# sparkpunk.net
KiCad netlist of a schematic drawn in EAGLE
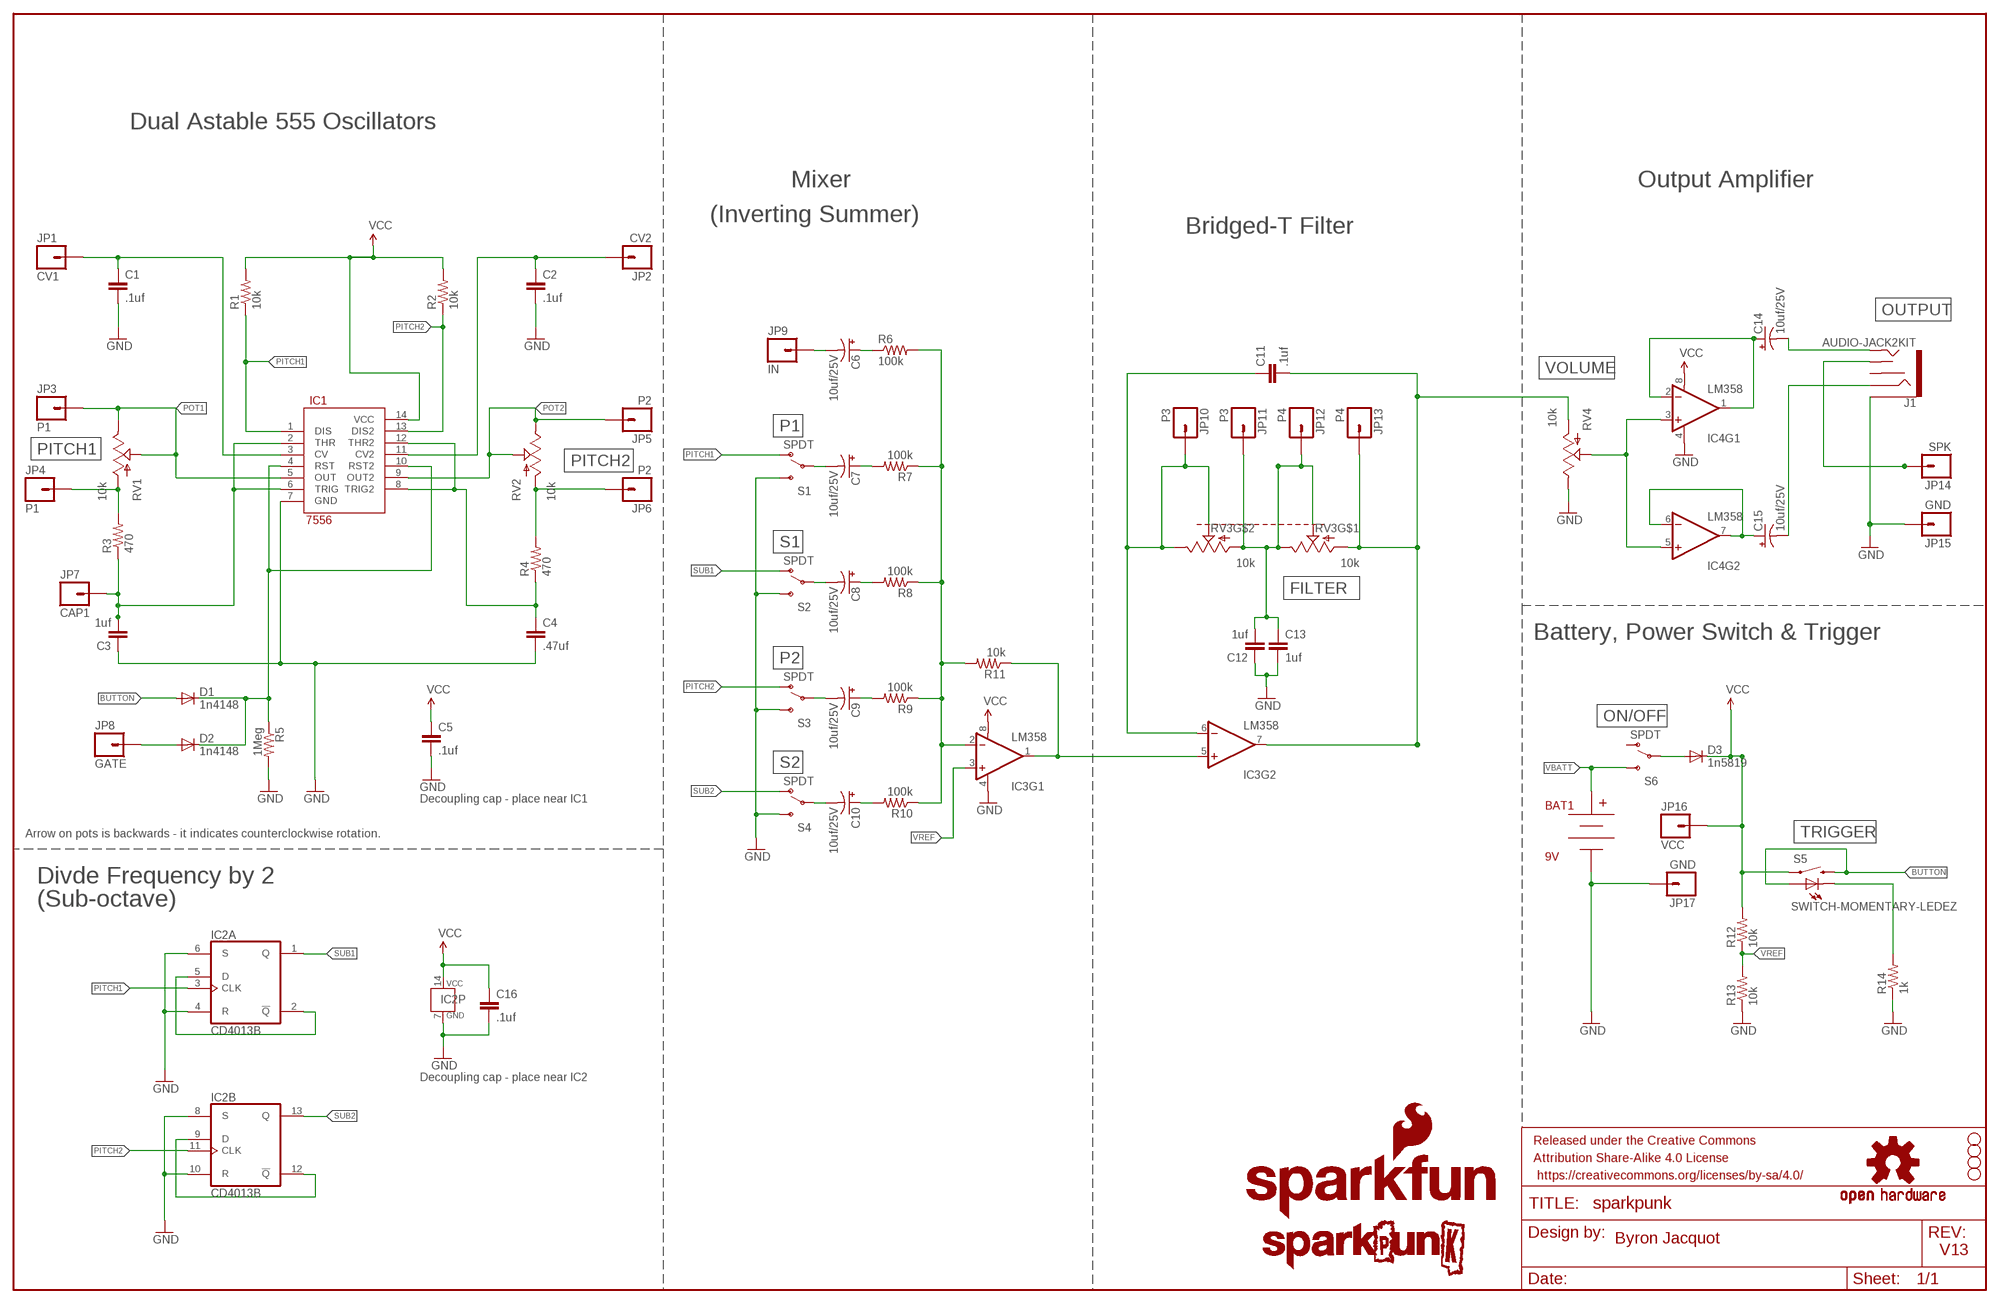
[diagram p0: schematic, sheet 1]

(export (version "E")
  (design (tool "Eeschema 10.0.6"))
  (components
    (comp (ref "BAT1")
      (value "9V")
      (footprint "eagle-import:BC9VPC_KIT")
      (libsource (lib "eagle-import") (part "BC9VPCKIT_SOLDERMASK"))
    )
    (comp (ref "C1")
      (value ".1uf")
      (footprint "eagle-import:CAP-PTH-SMALL-KIT")
      (libsource (lib "eagle-import") (part "CAPKIT"))
    )
    (comp (ref "C2")
      (value ".1uf")
      (footprint "eagle-import:CAP-PTH-SMALL-KIT")
      (libsource (lib "eagle-import") (part "CAPKIT"))
    )
    (comp (ref "C3")
      (value "1uf")
      (footprint "eagle-import:CAP-PTH-SMALL-KIT")
      (libsource (lib "eagle-import") (part "CAPKIT"))
    )
    (comp (ref "C4")
      (value ".47uf")
      (footprint "eagle-import:CAP-PTH-SMALL-KIT")
      (libsource (lib "eagle-import") (part "CAPKIT"))
    )
    (comp (ref "C5")
      (value ".1uf")
      (footprint "eagle-import:CAP-PTH-SMALL-KIT")
      (libsource (lib "eagle-import") (part "CAPKIT"))
    )
    (comp (ref "C6")
      (value "10uf/25V")
      (footprint "eagle-import:CPOL-RADIAL-10UF-25V-KIT")
      (libsource (lib "eagle-import") (part "10UF-25V-20%(PTH)KIT"))
    )
    (comp (ref "C7")
      (value "10uf/25V")
      (footprint "eagle-import:CPOL-RADIAL-10UF-25V-KIT")
      (libsource (lib "eagle-import") (part "10UF-25V-20%(PTH)KIT"))
    )
    (comp (ref "C8")
      (value "10uf/25V")
      (footprint "eagle-import:CPOL-RADIAL-10UF-25V-KIT")
      (libsource (lib "eagle-import") (part "10UF-25V-20%(PTH)KIT"))
    )
    (comp (ref "C9")
      (value "10uf/25V")
      (footprint "eagle-import:CPOL-RADIAL-10UF-25V-KIT")
      (libsource (lib "eagle-import") (part "10UF-25V-20%(PTH)KIT"))
    )
    (comp (ref "C10")
      (value "10uf/25V")
      (footprint "eagle-import:CPOL-RADIAL-10UF-25V-KIT")
      (libsource (lib "eagle-import") (part "10UF-25V-20%(PTH)KIT"))
    )
    (comp (ref "C11")
      (value ".1uf")
      (footprint "eagle-import:CAP-PTH-SMALL-KIT")
      (libsource (lib "eagle-import") (part "CAPKIT"))
    )
    (comp (ref "C12")
      (value "1uf")
      (footprint "eagle-import:CAP-PTH-SMALL-KIT")
      (libsource (lib "eagle-import") (part "CAPKIT"))
    )
    (comp (ref "C13")
      (value "1uf")
      (footprint "eagle-import:CAP-PTH-SMALL-KIT")
      (libsource (lib "eagle-import") (part "CAPKIT"))
    )
    (comp (ref "C14")
      (value "10uf/25V")
      (footprint "eagle-import:CPOL-RADIAL-10UF-25V-KIT")
      (libsource (lib "eagle-import") (part "10UF-25V-20%(PTH)KIT"))
    )
    (comp (ref "C15")
      (value "10uf/25V")
      (footprint "eagle-import:CPOL-RADIAL-10UF-25V-KIT")
      (libsource (lib "eagle-import") (part "10UF-25V-20%(PTH)KIT"))
    )
    (comp (ref "C16")
      (value ".1uf")
      (footprint "eagle-import:CAP-PTH-SMALL-KIT")
      (libsource (lib "eagle-import") (part "CAPKIT"))
    )
    (comp (ref "D1")
      (value "1n4148")
      (footprint "eagle-import:DIODE-1N4148-KIT")
      (libsource (lib "eagle-import") (part "DIODEKIT"))
    )
    (comp (ref "D2")
      (value "1n4148")
      (footprint "eagle-import:DIODE-1N4148-KIT")
      (libsource (lib "eagle-import") (part "DIODEKIT"))
    )
    (comp (ref "D3")
      (value "1n5819")
      (footprint "eagle-import:DIODE-1N4001-KIT")
      (libsource (lib "eagle-import") (part "DIODE"))
    )
    (comp (ref "FRAME1")
      (value "FRAME-LEDGER")
      (footprint "eagle-import:CREATIVE_COMMONS")
      (libsource (lib "eagle-import") (part "FRAME-LEDGER"))
    )
    (comp (ref "IC1")
      (value "7556")
      (footprint "eagle-import:DIL14-KIT")
      (libsource (lib "eagle-import") (part "556KIT"))
    )
    (comp (ref "IC2")
      (value "CD4013B")
      (footprint "eagle-import:DIL14-KIT")
      (libsource (lib "eagle-import") (part "CD4013"))
    )
    (comp (ref "IC3")
      (value "LM358")
      (footprint "eagle-import:DIP08-KIT")
      (libsource (lib "eagle-import") (part "LM358KIT"))
    )
    (comp (ref "IC4")
      (value "LM358")
      (footprint "eagle-import:DIP08-KIT")
      (libsource (lib "eagle-import") (part "LM358KIT"))
    )
    (comp (ref "J1")
      (value "AUDIO-JACK2KIT")
      (footprint "eagle-import:AUDIO-JACK-KIT")
      (libsource (lib "eagle-import") (part "AUDIO-JACK2KIT"))
    )
    (comp (ref "JP1")
      (value "CV1")
      (footprint "eagle-import:1X01NS")
      (libsource (lib "eagle-import") (part "M01SMDNS"))
    )
    (comp (ref "JP2")
      (value "CV2")
      (footprint "eagle-import:1X01NS")
      (libsource (lib "eagle-import") (part "M01SMDNS"))
    )
    (comp (ref "JP3")
      (value "P1")
      (footprint "eagle-import:1X01NS")
      (libsource (lib "eagle-import") (part "M01SMDNS"))
    )
    (comp (ref "JP4")
      (value "P1")
      (footprint "eagle-import:1X01NS")
      (libsource (lib "eagle-import") (part "M01SMDNS"))
    )
    (comp (ref "JP5")
      (value "P2")
      (footprint "eagle-import:1X01NS")
      (libsource (lib "eagle-import") (part "M01SMDNS"))
    )
    (comp (ref "JP6")
      (value "P2")
      (footprint "eagle-import:1X01NS")
      (libsource (lib "eagle-import") (part "M01SMDNS"))
    )
    (comp (ref "JP7")
      (value "CAP1")
      (footprint "eagle-import:1X01NS")
      (libsource (lib "eagle-import") (part "M01SMDNS"))
    )
    (comp (ref "JP8")
      (value "GATE")
      (footprint "eagle-import:1X01NS")
      (libsource (lib "eagle-import") (part "M01SMDNS"))
    )
    (comp (ref "JP9")
      (value "IN")
      (footprint "eagle-import:1X01NS")
      (libsource (lib "eagle-import") (part "M01SMDNS"))
    )
    (comp (ref "JP10")
      (value "P3")
      (footprint "eagle-import:1X01NS")
      (libsource (lib "eagle-import") (part "M01SMDNS"))
    )
    (comp (ref "JP11")
      (value "P3")
      (footprint "eagle-import:1X01NS")
      (libsource (lib "eagle-import") (part "M01SMDNS"))
    )
    (comp (ref "JP12")
      (value "P4")
      (footprint "eagle-import:1X01NS")
      (libsource (lib "eagle-import") (part "M01SMDNS"))
    )
    (comp (ref "JP13")
      (value "P4")
      (footprint "eagle-import:1X01NS")
      (libsource (lib "eagle-import") (part "M01SMDNS"))
    )
    (comp (ref "JP14")
      (value "SPK")
      (footprint "eagle-import:1X01NS")
      (libsource (lib "eagle-import") (part "M01SMDNS"))
    )
    (comp (ref "JP15")
      (value "GND")
      (footprint "eagle-import:1X01NS")
      (libsource (lib "eagle-import") (part "M01SMDNS"))
    )
    (comp (ref "JP16")
      (value "VCC")
      (footprint "eagle-import:1X01NS")
      (libsource (lib "eagle-import") (part "M01SMDNS"))
    )
    (comp (ref "JP17")
      (value "GND")
      (footprint "eagle-import:1X01NS")
      (libsource (lib "eagle-import") (part "M01SMDNS"))
    )
    (comp (ref "LOGO1")
      (value "SFE_LOGO_NAME_FLAME.2_INCH")
      (footprint "eagle-import:SFE_LOGO_NAME_FLAME_.2")
      (libsource (lib "eagle-import") (part "SFE_LOGO_NAME_FLAME.2_INCH"))
    )
    (comp (ref "LOGO2")
      (value "SPARKPUNK_LOGO.1INCH_TALL")
      (footprint "eagle-import:SPARKPUNK_LOGO_.1")
      (libsource (lib "eagle-import") (part "SPARKPUNK_LOGO.1INCH_TALL"))
    )
    (comp (ref "LOGO3")
      (value "OSHW-LOGOM")
      (footprint "eagle-import:OSHW-LOGO-M")
      (libsource (lib "eagle-import") (part "OSHW-LOGOM"))
    )
    (comp (ref "LOGO4")
      (value "OSHW-LOGOM")
      (footprint "eagle-import:OSHW-LOGO-M")
      (libsource (lib "eagle-import") (part "OSHW-LOGOM"))
    )
    (comp (ref "R1")
      (value "10k")
      (footprint "eagle-import:AXIAL-0.3EZ")
      (libsource (lib "eagle-import") (part "RESISTOREZ"))
    )
    (comp (ref "R2")
      (value "10k")
      (footprint "eagle-import:AXIAL-0.3EZ")
      (libsource (lib "eagle-import") (part "RESISTOREZ"))
    )
    (comp (ref "R3")
      (value "470")
      (footprint "eagle-import:AXIAL-0.3EZ")
      (libsource (lib "eagle-import") (part "RESISTOREZ"))
    )
    (comp (ref "R4")
      (value "470")
      (footprint "eagle-import:AXIAL-0.3EZ")
      (libsource (lib "eagle-import") (part "RESISTOREZ"))
    )
    (comp (ref "R5")
      (value "1Meg")
      (footprint "eagle-import:AXIAL-0.3EZ")
      (libsource (lib "eagle-import") (part "RESISTOREZ"))
    )
    (comp (ref "R6")
      (value "100k")
      (footprint "eagle-import:AXIAL-0.3EZ")
      (libsource (lib "eagle-import") (part "RESISTOREZ"))
    )
    (comp (ref "R7")
      (value "100k")
      (footprint "eagle-import:AXIAL-0.3EZ")
      (libsource (lib "eagle-import") (part "RESISTOREZ"))
    )
    (comp (ref "R8")
      (value "100k")
      (footprint "eagle-import:AXIAL-0.3EZ")
      (libsource (lib "eagle-import") (part "RESISTOREZ"))
    )
    (comp (ref "R9")
      (value "100k")
      (footprint "eagle-import:AXIAL-0.3EZ")
      (libsource (lib "eagle-import") (part "RESISTOREZ"))
    )
    (comp (ref "R10")
      (value "100k")
      (footprint "eagle-import:AXIAL-0.3EZ")
      (libsource (lib "eagle-import") (part "RESISTOREZ"))
    )
    (comp (ref "R11")
      (value "10k")
      (footprint "eagle-import:AXIAL-0.3EZ")
      (libsource (lib "eagle-import") (part "RESISTOREZ"))
    )
    (comp (ref "R12")
      (value "10k")
      (footprint "eagle-import:AXIAL-0.3EZ")
      (libsource (lib "eagle-import") (part "RESISTOREZ"))
    )
    (comp (ref "R13")
      (value "10k")
      (footprint "eagle-import:AXIAL-0.3EZ")
      (libsource (lib "eagle-import") (part "RESISTOREZ"))
    )
    (comp (ref "R14")
      (value "1k")
      (footprint "eagle-import:AXIAL-0.3EZ")
      (libsource (lib "eagle-import") (part "RESISTOREZ"))
    )
    (comp (ref "RV1")
      (value "10k")
      (footprint "eagle-import:ALPS_POT_KIT")
      (libsource (lib "eagle-import") (part "POTALPS-KIT"))
    )
    (comp (ref "RV2")
      (value "10k")
      (footprint "eagle-import:ALPS_POT_KIT")
      (libsource (lib "eagle-import") (part "POTALPS-KIT"))
    )
    (comp (ref "RV3")
      (value "10k")
      (footprint "eagle-import:POT_PANASONIC_DUAL_VERT_KIT")
      (fields (field (name "DIST") "digikey") (field (name "DIST_ID") " P2A5103-ND"))
      (libsource (lib "eagle-import") (part "POT_DUAL"))
    )
    (comp (ref "RV4")
      (value "10k")
      (footprint "eagle-import:ALPS_POT_KIT")
      (libsource (lib "eagle-import") (part "POTALPS-KIT"))
    )
    (comp (ref "S1")
      (value "SPDT")
      (footprint "eagle-import:SWITCH-SPDT_KIT")
      (libsource (lib "eagle-import") (part "SWITCH-SPDTKIT"))
    )
    (comp (ref "S2")
      (value "SPDT")
      (footprint "eagle-import:SWITCH-SPDT_KIT")
      (libsource (lib "eagle-import") (part "SWITCH-SPDTKIT"))
    )
    (comp (ref "S3")
      (value "SPDT")
      (footprint "eagle-import:SWITCH-SPDT_KIT")
      (libsource (lib "eagle-import") (part "SWITCH-SPDTKIT"))
    )
    (comp (ref "S4")
      (value "SPDT")
      (footprint "eagle-import:SWITCH-SPDT_KIT")
      (libsource (lib "eagle-import") (part "SWITCH-SPDTKIT"))
    )
    (comp (ref "S5")
      (value "SWITCH-MOMENTARY-LEDEZ")
      (footprint "eagle-import:TACTILE-PTH-LED-12MM-EZ")
      (libsource (lib "eagle-import") (part "SWITCH-MOMENTARY-LEDEZ"))
    )
    (comp (ref "S6")
      (value "SPDT")
      (footprint "eagle-import:SWITCH-SPDT_KIT")
      (libsource (lib "eagle-import") (part "SWITCH-SPDTKIT"))
    )
    (comp (ref "STANDOFF1")
      (value "STAND-OFF")
      (footprint "eagle-import:STAND-OFF")
      (libsource (lib "eagle-import") (part "STAND-OFF"))
    )
    (comp (ref "STANDOFF2")
      (value "STAND-OFF")
      (footprint "eagle-import:STAND-OFF")
      (libsource (lib "eagle-import") (part "STAND-OFF"))
    )
    (comp (ref "STANDOFF3")
      (value "STAND-OFF")
      (footprint "eagle-import:STAND-OFF")
      (libsource (lib "eagle-import") (part "STAND-OFF"))
    )
    (comp (ref "STANDOFF4")
      (value "STAND-OFF")
      (footprint "eagle-import:STAND-OFF")
      (libsource (lib "eagle-import") (part "STAND-OFF"))
    )
  )
  (nets
    (net (code "1") (name "BUTTON") (class "Default")
      (node (ref "D1") (pin "A") (pinfunction "A_A") (pintype "passive"))
      (node (ref "S5") (pin "2") (pinfunction "2_2") (pintype "passive"))
      (node (ref "S5") (pin "A") (pinfunction "A_A") (pintype "passive"))
    )
    (net (code "2") (name "GND") (class "Default")
      (node (ref "BAT1") (pin "V-") (pinfunction "V-_V-") (pintype "bidirectional"))
      (node (ref "C1") (pin "2") (pinfunction "2_2") (pintype "passive"))
      (node (ref "C12") (pin "1") (pinfunction "1_1") (pintype "passive"))
      (node (ref "C13") (pin "2") (pinfunction "2_2") (pintype "passive"))
      (node (ref "C16") (pin "2") (pinfunction "2_2") (pintype "passive"))
      (node (ref "C2") (pin "2") (pinfunction "2_2") (pintype "passive"))
      (node (ref "C3") (pin "1") (pinfunction "1_1") (pintype "passive"))
      (node (ref "C4") (pin "2") (pinfunction "2_2") (pintype "passive"))
      (node (ref "C5") (pin "2") (pinfunction "2_2") (pintype "passive"))
      (node (ref "IC1") (pin "7") (pinfunction "GND_7") (pintype "bidirectional"))
      (node (ref "IC2") (pin "10") (pinfunction "R_10") (pintype "input"))
      (node (ref "IC2") (pin "4") (pinfunction "R_4") (pintype "input"))
      (node (ref "IC2") (pin "6") (pinfunction "S_6") (pintype "input"))
      (node (ref "IC2") (pin "7") (pinfunction "GND_7") (pintype "power_in"))
      (node (ref "IC2") (pin "8") (pinfunction "S_8") (pintype "input"))
      (node (ref "IC3") (pin "4") (pinfunction "V-_4") (pintype "power_in"))
      (node (ref "IC4") (pin "4") (pinfunction "V-_4") (pintype "power_in"))
      (node (ref "J1") (pin "SLEEVE") (pinfunction "SLEEVE_SLEEVE") (pintype "bidirectional"))
      (node (ref "JP15") (pin "1") (pinfunction "1_1") (pintype "passive"))
      (node (ref "JP17") (pin "1") (pinfunction "1_1") (pintype "passive"))
      (node (ref "R13") (pin "P$1") (pinfunction "1_P$1") (pintype "passive"))
      (node (ref "R14") (pin "P$1") (pinfunction "1_P$1") (pintype "passive"))
      (node (ref "R5") (pin "P$2") (pinfunction "2_P$2") (pintype "passive"))
      (node (ref "RV4") (pin "P$1") (pinfunction "E_P$1") (pintype "passive"))
      (node (ref "S1") (pin "3") (pinfunction "S_3") (pintype "passive"))
      (node (ref "S2") (pin "3") (pinfunction "S_3") (pintype "passive"))
      (node (ref "S3") (pin "3") (pinfunction "S_3") (pintype "passive"))
      (node (ref "S4") (pin "3") (pinfunction "S_3") (pintype "passive"))
    )
    (net (code "3") (name "Net-(C6-+)") (class "Default")
      (node (ref "C6") (pin "1") (pinfunction "+_1") (pintype "passive"))
      (node (ref "R6") (pin "P$1") (pinfunction "1_P$1") (pintype "passive"))
    )
    (net (code "4") (name "Net-(C6--)") (class "Default")
      (node (ref "C6") (pin "2") (pinfunction "-_2") (pintype "passive"))
      (node (ref "JP9") (pin "1") (pinfunction "1_1") (pintype "passive"))
    )
    (net (code "5") (name "Net-(C7-+)") (class "Default")
      (node (ref "C7") (pin "1") (pinfunction "+_1") (pintype "passive"))
      (node (ref "R7") (pin "P$2") (pinfunction "2_P$2") (pintype "passive"))
    )
    (net (code "6") (name "Net-(C7--)") (class "Default")
      (node (ref "C7") (pin "2") (pinfunction "-_2") (pintype "passive"))
      (node (ref "S1") (pin "2") (pinfunction "P_2") (pintype "passive"))
    )
    (net (code "7") (name "Net-(C8-+)") (class "Default")
      (node (ref "C8") (pin "1") (pinfunction "+_1") (pintype "passive"))
      (node (ref "R8") (pin "P$2") (pinfunction "2_P$2") (pintype "passive"))
    )
    (net (code "8") (name "Net-(C8--)") (class "Default")
      (node (ref "C8") (pin "2") (pinfunction "-_2") (pintype "passive"))
      (node (ref "S2") (pin "2") (pinfunction "P_2") (pintype "passive"))
    )
    (net (code "9") (name "Net-(C9-+)") (class "Default")
      (node (ref "C9") (pin "1") (pinfunction "+_1") (pintype "passive"))
      (node (ref "R9") (pin "P$2") (pinfunction "2_P$2") (pintype "passive"))
    )
    (net (code "10") (name "Net-(C9--)") (class "Default")
      (node (ref "C9") (pin "2") (pinfunction "-_2") (pintype "passive"))
      (node (ref "S3") (pin "2") (pinfunction "P_2") (pintype "passive"))
    )
    (net (code "11") (name "Net-(C10-+)") (class "Default")
      (node (ref "C10") (pin "1") (pinfunction "+_1") (pintype "passive"))
      (node (ref "R10") (pin "P$2") (pinfunction "2_P$2") (pintype "passive"))
    )
    (net (code "12") (name "Net-(C10--)") (class "Default")
      (node (ref "C10") (pin "2") (pinfunction "-_2") (pintype "passive"))
      (node (ref "S4") (pin "2") (pinfunction "P_2") (pintype "passive"))
    )
    (net (code "13") (name "Net-(C14-+)") (class "Default")
      (node (ref "C14") (pin "1") (pinfunction "+_1") (pintype "passive"))
      (node (ref "IC4") (pin "1") (pinfunction "OUT_1") (pintype "output"))
      (node (ref "IC4") (pin "2") (pinfunction "-IN_2") (pintype "input"))
    )
    (net (code "14") (name "Net-(C14--)") (class "Default")
      (node (ref "C14") (pin "2") (pinfunction "-_2") (pintype "passive"))
      (node (ref "J1") (pin "TIP") (pinfunction "TIP_TIP") (pintype "bidirectional"))
    )
    (net (code "15") (name "Net-(C15-+)") (class "Default")
      (node (ref "C15") (pin "1") (pinfunction "+_1") (pintype "passive"))
      (node (ref "IC4") (pin "6") (pinfunction "-IN_6") (pintype "input"))
      (node (ref "IC4") (pin "7") (pinfunction "OUT_7") (pintype "output"))
    )
    (net (code "16") (name "Net-(C15--)") (class "Default")
      (node (ref "C15") (pin "2") (pinfunction "-_2") (pintype "passive"))
      (node (ref "J1") (pin "RING") (pinfunction "RING_RING") (pintype "bidirectional"))
    )
    (net (code "17") (name "Net-(D2-PadA)") (class "Default")
      (node (ref "D2") (pin "A") (pinfunction "A_A") (pintype "passive"))
      (node (ref "JP8") (pin "1") (pinfunction "1_1") (pintype "passive"))
    )
    (net (code "18") (name "Net-(IC1-CV)") (class "Default")
      (node (ref "C1") (pin "1") (pinfunction "1_1") (pintype "passive"))
      (node (ref "IC1") (pin "3") (pinfunction "CV_3") (pintype "bidirectional"))
      (node (ref "JP1") (pin "1") (pinfunction "1_1") (pintype "passive"))
    )
    (net (code "19") (name "Net-(IC1-CV2)") (class "Default")
      (node (ref "C2") (pin "1") (pinfunction "1_1") (pintype "passive"))
      (node (ref "IC1") (pin "11") (pinfunction "CV2_11") (pintype "bidirectional"))
      (node (ref "JP2") (pin "1") (pinfunction "1_1") (pintype "passive"))
    )
    (net (code "20") (name "Net-(IC1-RST)") (class "Default")
      (node (ref "D1") (pin "C") (pinfunction "C_C") (pintype "passive"))
      (node (ref "D2") (pin "C") (pinfunction "C_C") (pintype "passive"))
      (node (ref "IC1") (pin "10") (pinfunction "RST2_10") (pintype "bidirectional"))
      (node (ref "IC1") (pin "4") (pinfunction "RST_4") (pintype "bidirectional"))
      (node (ref "R5") (pin "P$1") (pinfunction "1_P$1") (pintype "passive"))
    )
    (net (code "21") (name "Net-(IC1-THR)") (class "Default")
      (node (ref "C3") (pin "2") (pinfunction "2_2") (pintype "passive"))
      (node (ref "IC1") (pin "2") (pinfunction "THR_2") (pintype "bidirectional"))
      (node (ref "IC1") (pin "6") (pinfunction "TRIG_6") (pintype "bidirectional"))
      (node (ref "JP7") (pin "1") (pinfunction "1_1") (pintype "passive"))
      (node (ref "R3") (pin "P$1") (pinfunction "1_P$1") (pintype "passive"))
    )
    (net (code "22") (name "Net-(IC1-THR2)") (class "Default")
      (node (ref "C4") (pin "1") (pinfunction "1_1") (pintype "passive"))
      (node (ref "IC1") (pin "12") (pinfunction "THR2_12") (pintype "bidirectional"))
      (node (ref "IC1") (pin "8") (pinfunction "TRIG2_8") (pintype "bidirectional"))
      (node (ref "R4") (pin "P$1") (pinfunction "1_P$1") (pintype "passive"))
    )
    (net (code "23") (name "Net-(IC2A-D)") (class "Default")
      (node (ref "IC2") (pin "2") (pinfunction "~{Q}_2") (pintype "output"))
      (node (ref "IC2") (pin "5") (pinfunction "D_5") (pintype "input"))
    )
    (net (code "24") (name "Net-(IC2B-D)") (class "Default")
      (node (ref "IC2") (pin "12") (pinfunction "~{Q}_12") (pintype "output"))
      (node (ref "IC2") (pin "9") (pinfunction "D_9") (pintype "input"))
    )
    (net (code "25") (name "Net-(IC3A--IN)") (class "Default")
      (node (ref "IC3") (pin "2") (pinfunction "-IN_2") (pintype "input"))
      (node (ref "R10") (pin "P$1") (pinfunction "1_P$1") (pintype "passive"))
      (node (ref "R11") (pin "P$2") (pinfunction "2_P$2") (pintype "passive"))
      (node (ref "R6") (pin "P$2") (pinfunction "2_P$2") (pintype "passive"))
      (node (ref "R7") (pin "P$1") (pinfunction "1_P$1") (pintype "passive"))
      (node (ref "R8") (pin "P$1") (pinfunction "1_P$1") (pintype "passive"))
      (node (ref "R9") (pin "P$1") (pinfunction "1_P$1") (pintype "passive"))
    )
    (net (code "26") (name "Net-(IC3A-OUT)") (class "Default")
      (node (ref "IC3") (pin "1") (pinfunction "OUT_1") (pintype "output"))
      (node (ref "IC3") (pin "5") (pinfunction "+IN_5") (pintype "input"))
      (node (ref "R11") (pin "P$1") (pinfunction "1_P$1") (pintype "passive"))
    )
    (net (code "27") (name "Net-(IC3B--IN)") (class "Default")
      (node (ref "C11") (pin "1") (pinfunction "1_1") (pintype "passive"))
      (node (ref "IC3") (pin "6") (pinfunction "-IN_6") (pintype "input"))
      (node (ref "JP10") (pin "1") (pinfunction "1_1") (pintype "passive"))
      (node (ref "RV3") (pin "B1") (pinfunction "E_B1") (pintype "passive"))
      (node (ref "RV3") (pin "B2") (pinfunction "S_B2") (pintype "passive"))
    )
    (net (code "28") (name "Net-(IC3B-OUT)") (class "Default")
      (node (ref "C11") (pin "2") (pinfunction "2_2") (pintype "passive"))
      (node (ref "IC3") (pin "7") (pinfunction "OUT_7") (pintype "output"))
      (node (ref "JP13") (pin "1") (pinfunction "1_1") (pintype "passive"))
      (node (ref "RV3") (pin "A3") (pinfunction "A_A3") (pintype "passive"))
      (node (ref "RV4") (pin "P$3") (pinfunction "A_P$3") (pintype "passive"))
    )
    (net (code "29") (name "Net-(IC4A-+IN)") (class "Default")
      (node (ref "IC4") (pin "3") (pinfunction "+IN_3") (pintype "input"))
      (node (ref "IC4") (pin "5") (pinfunction "+IN_5") (pintype "input"))
      (node (ref "RV4") (pin "P$2") (pinfunction "S_P$2") (pintype "passive"))
    )
    (net (code "30") (name "Net-(J1-PadTSH)") (class "Default")
      (node (ref "J1") (pin "TSH") (pinfunction "TSH_TSH") (pintype "bidirectional"))
      (node (ref "JP14") (pin "1") (pinfunction "1_1") (pintype "passive"))
    )
    (net (code "31") (name "Net-(R3-2)") (class "Default")
      (node (ref "JP4") (pin "1") (pinfunction "1_1") (pintype "passive"))
      (node (ref "R3") (pin "P$2") (pinfunction "2_P$2") (pintype "passive"))
      (node (ref "RV1") (pin "P$3") (pinfunction "A_P$3") (pintype "passive"))
    )
    (net (code "32") (name "Net-(R4-2)") (class "Default")
      (node (ref "JP6") (pin "1") (pinfunction "1_1") (pintype "passive"))
      (node (ref "R4") (pin "P$2") (pinfunction "2_P$2") (pintype "passive"))
      (node (ref "RV2") (pin "P$3") (pinfunction "A_P$3") (pintype "passive"))
    )
    (net (code "33") (name "Net-(R14-2)") (class "Default")
      (node (ref "R14") (pin "P$2") (pinfunction "2_P$2") (pintype "passive"))
      (node (ref "S5") (pin "C") (pinfunction "C_C") (pintype "passive"))
    )
    (net (code "34") (name "Net-(RV3A-E)") (class "Default")
      (node (ref "C12") (pin "2") (pinfunction "2_2") (pintype "passive"))
      (node (ref "C13") (pin "1") (pinfunction "1_1") (pintype "passive"))
      (node (ref "JP11") (pin "1") (pinfunction "1_1") (pintype "passive"))
      (node (ref "JP12") (pin "1") (pinfunction "1_1") (pintype "passive"))
      (node (ref "RV3") (pin "A1") (pinfunction "E_A1") (pintype "passive"))
      (node (ref "RV3") (pin "A2") (pinfunction "S_A2") (pintype "passive"))
      (node (ref "RV3") (pin "B3") (pinfunction "A_B3") (pintype "passive"))
    )
    (net (code "35") (name "Net-(S6-P)") (class "Default")
      (node (ref "D3") (pin "A") (pinfunction "A_A") (pintype "passive"))
      (node (ref "S6") (pin "2") (pinfunction "P_2") (pintype "passive"))
    )
    (net (code "36") (name "PITCH1") (class "Default")
      (node (ref "IC1") (pin "1") (pinfunction "DIS_1") (pintype "bidirectional"))
      (node (ref "IC2") (pin "3") (pinfunction "CLK_3") (pintype "input"))
      (node (ref "R1") (pin "P$1") (pinfunction "1_P$1") (pintype "passive"))
      (node (ref "S1") (pin "1") (pinfunction "O_1") (pintype "passive"))
    )
    (net (code "37") (name "PITCH2") (class "Default")
      (node (ref "IC1") (pin "13") (pinfunction "DIS2_13") (pintype "bidirectional"))
      (node (ref "IC2") (pin "11") (pinfunction "CLK_11") (pintype "input"))
      (node (ref "R2") (pin "P$1") (pinfunction "1_P$1") (pintype "passive"))
      (node (ref "S3") (pin "1") (pinfunction "O_1") (pintype "passive"))
    )
    (net (code "38") (name "POT1") (class "Default")
      (node (ref "IC1") (pin "5") (pinfunction "OUT_5") (pintype "bidirectional"))
      (node (ref "JP3") (pin "1") (pinfunction "1_1") (pintype "passive"))
      (node (ref "RV1") (pin "P$1") (pinfunction "E_P$1") (pintype "passive"))
      (node (ref "RV1") (pin "P$2") (pinfunction "S_P$2") (pintype "passive"))
    )
    (net (code "39") (name "POT2") (class "Default")
      (node (ref "IC1") (pin "9") (pinfunction "OUT2_9") (pintype "bidirectional"))
      (node (ref "JP5") (pin "1") (pinfunction "1_1") (pintype "passive"))
      (node (ref "RV2") (pin "P$1") (pinfunction "E_P$1") (pintype "passive"))
      (node (ref "RV2") (pin "P$2") (pinfunction "S_P$2") (pintype "passive"))
    )
    (net (code "40") (name "SUB1") (class "Default")
      (node (ref "IC2") (pin "1") (pinfunction "Q_1") (pintype "output"))
      (node (ref "S2") (pin "1") (pinfunction "O_1") (pintype "passive"))
    )
    (net (code "41") (name "SUB2") (class "Default")
      (node (ref "IC2") (pin "13") (pinfunction "Q_13") (pintype "output"))
      (node (ref "S4") (pin "1") (pinfunction "O_1") (pintype "passive"))
    )
    (net (code "42") (name "VBATT") (class "Default")
      (node (ref "BAT1") (pin "V+") (pinfunction "V+_V+") (pintype "bidirectional"))
      (node (ref "S6") (pin "3") (pinfunction "S_3") (pintype "passive"))
    )
    (net (code "43") (name "VCC") (class "Default")
      (node (ref "C16") (pin "1") (pinfunction "1_1") (pintype "passive"))
      (node (ref "C5") (pin "1") (pinfunction "1_1") (pintype "passive"))
      (node (ref "D3") (pin "C") (pinfunction "C_C") (pintype "passive"))
      (node (ref "IC1") (pin "14") (pinfunction "VCC_14") (pintype "bidirectional"))
      (node (ref "IC2") (pin "14") (pinfunction "VCC_14") (pintype "power_in"))
      (node (ref "IC3") (pin "8") (pinfunction "V+_8") (pintype "power_in"))
      (node (ref "IC4") (pin "8") (pinfunction "V+_8") (pintype "power_in"))
      (node (ref "JP16") (pin "1") (pinfunction "1_1") (pintype "passive"))
      (node (ref "R1") (pin "P$2") (pinfunction "2_P$2") (pintype "passive"))
      (node (ref "R12") (pin "P$2") (pinfunction "2_P$2") (pintype "passive"))
      (node (ref "R2") (pin "P$2") (pinfunction "2_P$2") (pintype "passive"))
      (node (ref "S5") (pin "4") (pinfunction "1_4") (pintype "passive"))
    )
    (net (code "44") (name "VREF") (class "Default")
      (node (ref "IC3") (pin "3") (pinfunction "+IN_3") (pintype "input"))
      (node (ref "R12") (pin "P$1") (pinfunction "1_P$1") (pintype "passive"))
      (node (ref "R13") (pin "P$2") (pinfunction "2_P$2") (pintype "passive"))
    )
    (net (code "45") (name "unconnected-(J1-PadRSH)") (class "Default")
      (node (ref "J1") (pin "RSH") (pinfunction "RSH_RSH") (pintype "bidirectional"))
    )
    (net (code "46") (name "unconnected-(S6-O-Pad1)") (class "Default")
      (node (ref "S6") (pin "1") (pinfunction "O_1") (pintype "passive"))
    )
  )
)
